# Led_Green_Direct.net
KiCad netlist of a schematic drawn in Altium Designer
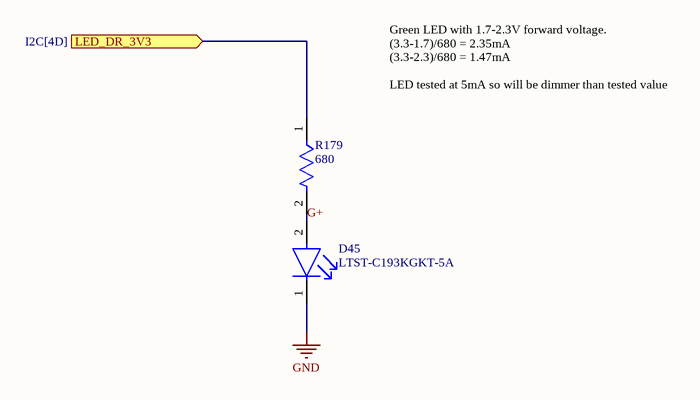
[diagram p0:  Led_Green_Direct.SchDoc]

(export (version "E")
  (design (tool "Eeschema 10.0.6"))
  (components
    (comp (ref "D45")
      (value "LTST-C193KGKT-5A")
      (footprint "FP-LTST-C193KGKT-5A-MFG")
      (description "LED yellow green 0603 wavelength 567.5~576.5nm light intensity 4.5~28mcd Front Mounting")
      (libsource (lib "HIL RIG FYP") (part "8706943c75ba83719d021d2fdc84c58"))
    )
    (comp (ref "R179")
      (value "680")
      (footprint "FP-CRCW0603-e3-IPC_C")
      (description "Fixed Resistor, Metal Glaze/Thick Film, 0.1W, 680ohm, 75V, 5% +/-Tol, Surface Mount, 0603")
      (fields (field (name "TOLERANCE") "5%") (field (name "Comment") "CRCW0603680RJNEA"))
      (libsource (lib "HIL RIG FYP") (part "1029c3af85768c4190bb7ad29bc67b5"))
    )
  )
  (nets
    (net (code "1") (name "/G+") (class "Default")
      (node (ref "D45") (pin "2") (pinfunction "A_2") (pintype "passive"))
      (node (ref "R179") (pin "2") (pinfunction "2_2") (pintype "passive"))
    )
    (net (code "2") (name "/LED_DR_3V3") (class "Default")
      (node (ref "R179") (pin "1") (pinfunction "1_1") (pintype "passive"))
    )
    (net (code "3") (name "GND") (class "Default")
      (node (ref "D45") (pin "1") (pinfunction "C_1") (pintype "passive"))
    )
  )
)
